# DO.net
KiCad netlist of a schematic drawn in Altium Designer
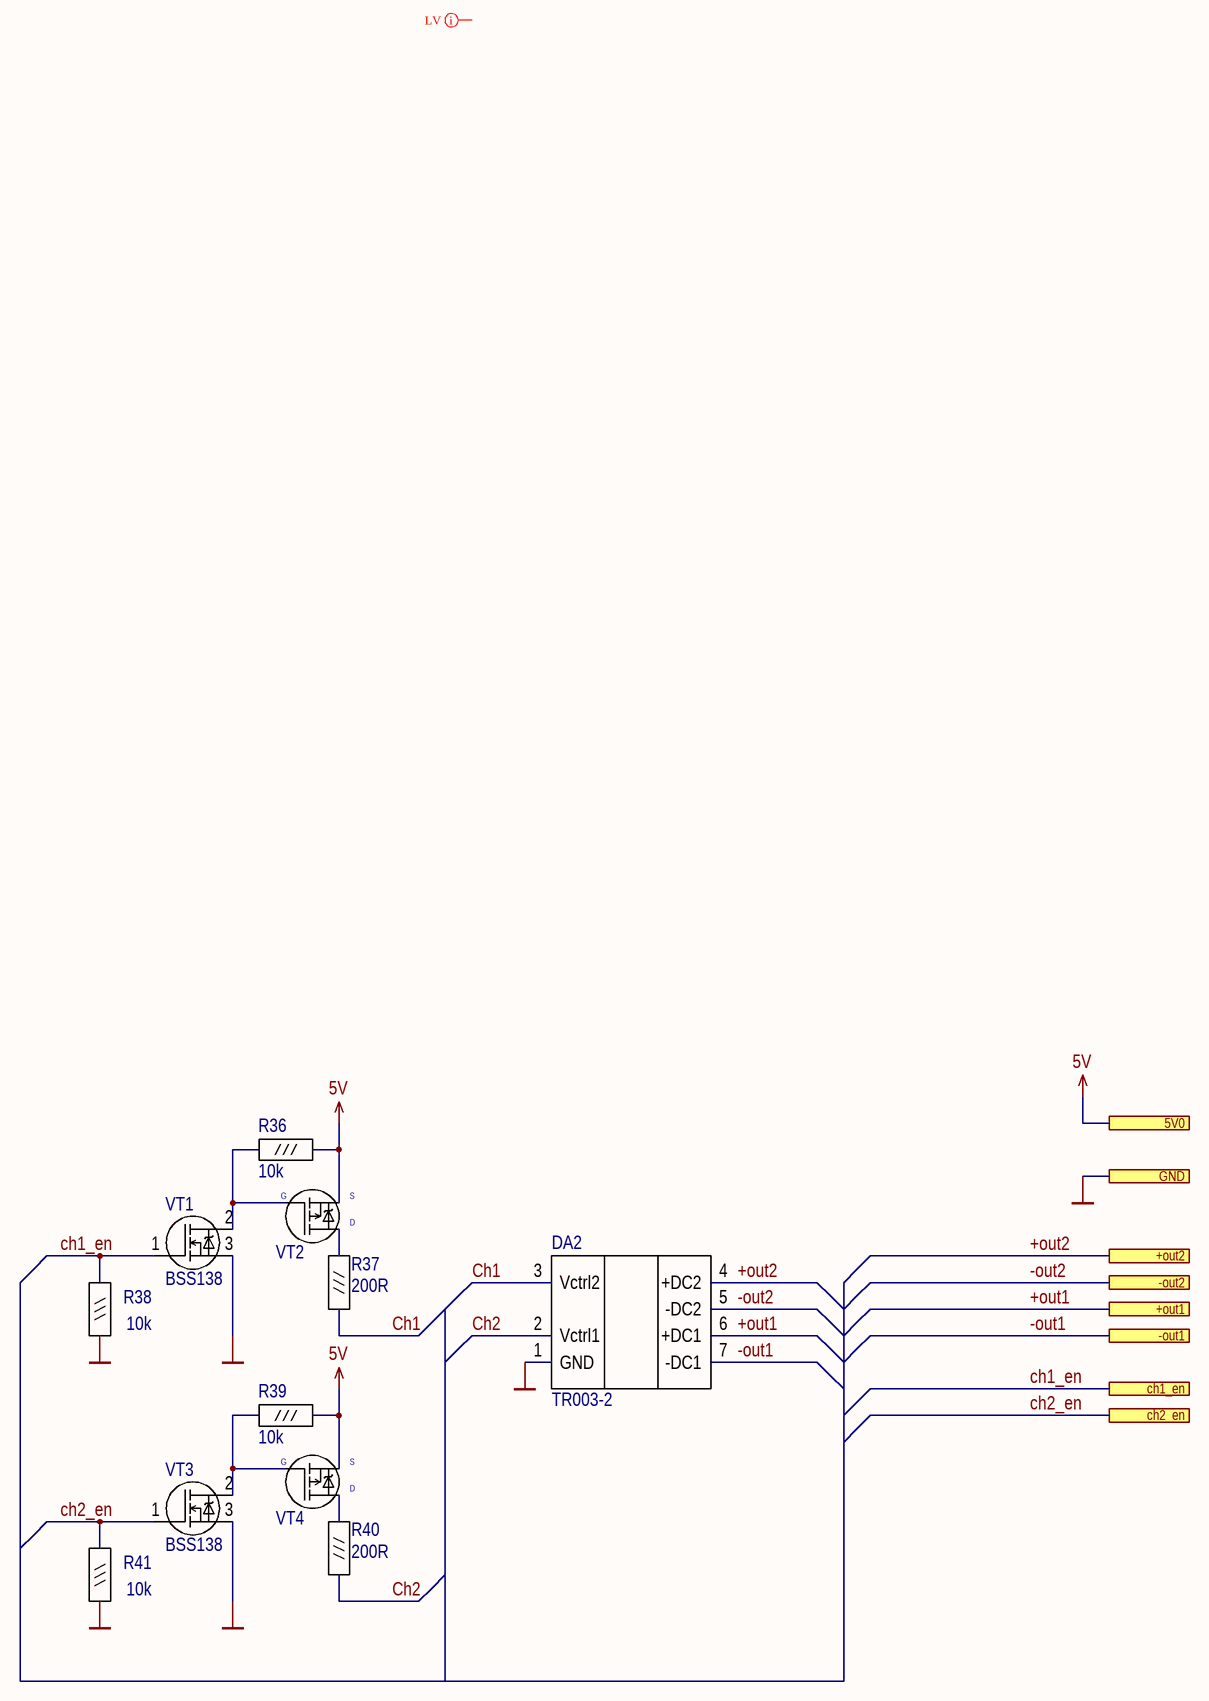
[diagram p0: DO.SchDoc]

(export (version "E")
  (design (tool "Eeschema 10.0.6"))
  (components
    (comp (ref "DA2") (value "TR003-2") (footprint "TR003-2") (libsource (lib "DB_IC") (part "TR003-2")))
    (comp (ref "R36")
      (value "10k")
      (footprint "R0603")
      (description "10 kOhms ±5% 0.1W, 1/10W Chip Resistor 0603 (1608 Metric) Moisture Resistant Thick Film")
      (fields (field (name "MPN") "RC0603JR-0710kL") (field (name "TOLERANCE") "5%"))
      (libsource (lib "DB_res_cap_ind") (part "R0603"))
    )
    (comp (ref "R37")
      (value "200R")
      (footprint "R0603")
      (description "200 Ohms ±5% 0.1W, 1/10W Chip Resistor 0603 (1608 Metric) Moisture Resistant Thick Film")
      (fields (field (name "MPN") "RC0603JR-07200RL") (field (name "TOLERANCE") "5%"))
      (libsource (lib "DB_res_cap_ind") (part "R0603"))
    )
    (comp (ref "R38")
      (value "10k")
      (footprint "R0603")
      (description "10 kOhms ±5% 0.1W, 1/10W Chip Resistor 0603 (1608 Metric) Moisture Resistant Thick Film")
      (fields (field (name "MPN") "RC0603JR-0710kL") (field (name "TOLERANCE") "5%"))
      (libsource (lib "DB_res_cap_ind") (part "R0603"))
    )
    (comp (ref "R39")
      (value "10k")
      (footprint "R0603")
      (description "10 kOhms ±5% 0.1W, 1/10W Chip Resistor 0603 (1608 Metric) Moisture Resistant Thick Film")
      (fields (field (name "MPN") "RC0603JR-0710kL") (field (name "TOLERANCE") "5%"))
      (libsource (lib "DB_res_cap_ind") (part "R0603"))
    )
    (comp (ref "R40")
      (value "200R")
      (footprint "R0603")
      (description "200 Ohms ±5% 0.1W, 1/10W Chip Resistor 0603 (1608 Metric) Moisture Resistant Thick Film")
      (fields (field (name "MPN") "RC0603JR-07200RL") (field (name "TOLERANCE") "5%"))
      (libsource (lib "DB_res_cap_ind") (part "R0603"))
    )
    (comp (ref "R41")
      (value "10k")
      (footprint "R0603")
      (description "10 kOhms ±5% 0.1W, 1/10W Chip Resistor 0603 (1608 Metric) Moisture Resistant Thick Film")
      (fields (field (name "MPN") "RC0603JR-0710kL") (field (name "TOLERANCE") "5%"))
      (libsource (lib "DB_res_cap_ind") (part "R0603"))
    )
    (comp (ref "VT1")
      (value "BSS138")
      (footprint "SOT23-3")
      (description "N-Channel 50V 200mA (Ta) 300mW (Ta) Surface Mount SOT-23-3")
      (fields (field (name "MANUFACTURER") "Diodes Incorporated"))
      (libsource (lib "DB_the_rest") (part "N_CH_GSD"))
    )
    (comp (ref "VT2")
      (value "AO3401A")
      (footprint "sot23-3")
      (description "P-Channel 30V 4A (Ta) 1.4W (Ta) Surface Mount SOT-23-3L")
      (fields (field (name "MANUFACTURER") "Infineon Technologies"))
      (libsource (lib "DB_the_rest") (part "P_CH3"))
    )
    (comp (ref "VT3")
      (value "BSS138")
      (footprint "SOT23-3")
      (description "N-Channel 50V 200mA (Ta) 300mW (Ta) Surface Mount SOT-23-3")
      (fields (field (name "MANUFACTURER") "Diodes Incorporated"))
      (libsource (lib "DB_the_rest") (part "N_CH_GSD"))
    )
    (comp (ref "VT4")
      (value "AO3401A")
      (footprint "sot23-3")
      (description "P-Channel 30V 4A (Ta) 1.4W (Ta) Surface Mount SOT-23-3L")
      (fields (field (name "MANUFACTURER") "Infineon Technologies"))
      (libsource (lib "DB_the_rest") (part "P_CH3"))
    )
  )
  (nets
    (net (code "1") (name "/+out1") (class "Default")
      (node (ref "DA2") (pin "6") (pinfunction "+DC1_6") (pintype "passive"))
    )
    (net (code "2") (name "/+out2") (class "Default")
      (node (ref "DA2") (pin "4") (pinfunction "+DC2_4") (pintype "passive"))
    )
    (net (code "3") (name "/-out1") (class "Default")
      (node (ref "DA2") (pin "7") (pinfunction "-DC1_7") (pintype "passive"))
    )
    (net (code "4") (name "/-out2") (class "Default")
      (node (ref "DA2") (pin "5") (pinfunction "-DC2_5") (pintype "passive"))
    )
    (net (code "5") (name "/Ch1") (class "Default")
      (node (ref "DA2") (pin "3") (pinfunction "Vctrl2_3") (pintype "passive"))
      (node (ref "R37") (pin "1") (pinfunction "1_1") (pintype "passive"))
    )
    (net (code "6") (name "/Ch2") (class "Default")
      (node (ref "DA2") (pin "2") (pinfunction "Vctrl1_2") (pintype "passive"))
      (node (ref "R40") (pin "1") (pinfunction "1_1") (pintype "passive"))
    )
    (net (code "7") (name "/ch1_en") (class "Default")
      (node (ref "R38") (pin "2") (pinfunction "2_2") (pintype "passive"))
      (node (ref "VT1") (pin "1") (pinfunction "G_1") (pintype "passive"))
    )
    (net (code "8") (name "/ch2_en") (class "Default")
      (node (ref "R41") (pin "2") (pinfunction "2_2") (pintype "passive"))
      (node (ref "VT3") (pin "1") (pinfunction "G_1") (pintype "passive"))
    )
    (net (code "9") (name "5V") (class "Default")
      (node (ref "R36") (pin "1") (pinfunction "1_1") (pintype "passive"))
      (node (ref "R39") (pin "1") (pinfunction "1_1") (pintype "passive"))
      (node (ref "VT2") (pin "2") (pinfunction "S_2") (pintype "passive"))
      (node (ref "VT4") (pin "2") (pinfunction "S_2") (pintype "passive"))
    )
    (net (code "10") (name "GND") (class "Default")
      (node (ref "DA2") (pin "1") (pinfunction "GND_1") (pintype "passive"))
      (node (ref "R38") (pin "1") (pinfunction "1_1") (pintype "passive"))
      (node (ref "R41") (pin "1") (pinfunction "1_1") (pintype "passive"))
      (node (ref "VT1") (pin "3") (pinfunction "S_3") (pintype "passive"))
      (node (ref "VT3") (pin "3") (pinfunction "S_3") (pintype "passive"))
    )
    (net (code "11") (name "Net-(VT1-D)") (class "Default")
      (node (ref "R36") (pin "2") (pinfunction "2_2") (pintype "passive"))
      (node (ref "VT1") (pin "2") (pinfunction "D_2") (pintype "passive"))
      (node (ref "VT2") (pin "1") (pinfunction "G_1") (pintype "passive"))
    )
    (net (code "12") (name "Net-(VT2-D)") (class "Default")
      (node (ref "R37") (pin "2") (pinfunction "2_2") (pintype "passive"))
      (node (ref "VT2") (pin "3") (pinfunction "D_3") (pintype "passive"))
    )
    (net (code "13") (name "Net-(VT3-D)") (class "Default")
      (node (ref "R39") (pin "2") (pinfunction "2_2") (pintype "passive"))
      (node (ref "VT3") (pin "2") (pinfunction "D_2") (pintype "passive"))
      (node (ref "VT4") (pin "1") (pinfunction "G_1") (pintype "passive"))
    )
    (net (code "14") (name "Net-(VT4-D)") (class "Default")
      (node (ref "R40") (pin "2") (pinfunction "2_2") (pintype "passive"))
      (node (ref "VT4") (pin "3") (pinfunction "D_3") (pintype "passive"))
    )
  )
)
